# DigitalCapture.net
KiCad netlist of a schematic drawn in Altium Designer
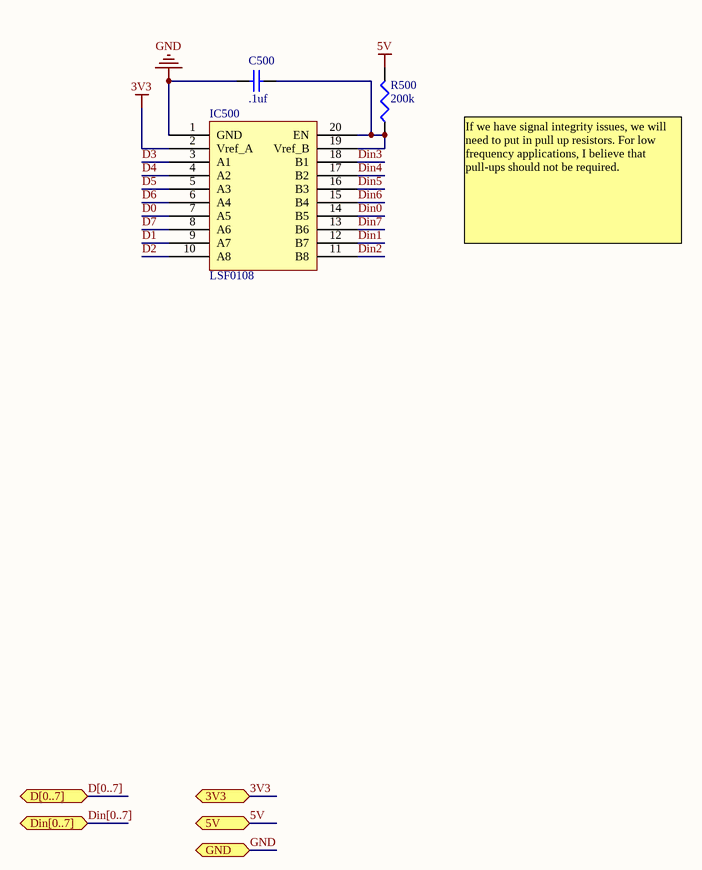
[diagram p0: DigitalCapture.SchDoc]

(export (version "E")
  (design (tool "Eeschema 10.0.6"))
  (components
    (comp (ref "C500")
      (value ".1uf")
      (footprint "SMD0603")
      (description "Ceramic Chip Capacitor")
      (fields (field (name "Comment") "Cap"))
      (libsource (lib "Components") (part "Capacitor Ceramic"))
    )
    (comp (ref "IC500")
      (value "LSF0108")
      (footprint "TSSOP-20")
      (description "8 bit 5V to 3.3V level shifter")
      (libsource (lib "Components") (part "LSF0108"))
    )
    (comp (ref "R500")
      (value "200k")
      (footprint "SMD0603")
      (description "Resistor")
      (fields (field (name "Comment") "Res"))
      (libsource (lib "Components") (part "Resistor"))
    )
  )
  (nets
    (net (code "1") (name "/D0") (class "Default")
      (node (ref "IC500") (pin "7") (pinfunction "A5_7") (pintype "passive"))
    )
    (net (code "2") (name "/D1") (class "Default")
      (node (ref "IC500") (pin "9") (pinfunction "A7_9") (pintype "passive"))
    )
    (net (code "3") (name "/D2") (class "Default")
      (node (ref "IC500") (pin "10") (pinfunction "A8_10") (pintype "passive"))
    )
    (net (code "4") (name "/D3") (class "Default")
      (node (ref "IC500") (pin "3") (pinfunction "A1_3") (pintype "passive"))
    )
    (net (code "5") (name "/D4") (class "Default")
      (node (ref "IC500") (pin "4") (pinfunction "A2_4") (pintype "passive"))
    )
    (net (code "6") (name "/D5") (class "Default")
      (node (ref "IC500") (pin "5") (pinfunction "A3_5") (pintype "passive"))
    )
    (net (code "7") (name "/D6") (class "Default")
      (node (ref "IC500") (pin "6") (pinfunction "A4_6") (pintype "passive"))
    )
    (net (code "8") (name "/D7") (class "Default")
      (node (ref "IC500") (pin "8") (pinfunction "A6_8") (pintype "passive"))
    )
    (net (code "10") (name "/Din0") (class "Default")
      (node (ref "IC500") (pin "14") (pinfunction "B5_14") (pintype "passive"))
    )
    (net (code "11") (name "/Din1") (class "Default")
      (node (ref "IC500") (pin "12") (pinfunction "B7_12") (pintype "passive"))
    )
    (net (code "12") (name "/Din2") (class "Default")
      (node (ref "IC500") (pin "11") (pinfunction "B8_11") (pintype "passive"))
    )
    (net (code "13") (name "/Din3") (class "Default")
      (node (ref "IC500") (pin "18") (pinfunction "B1_18") (pintype "passive"))
    )
    (net (code "14") (name "/Din4") (class "Default")
      (node (ref "IC500") (pin "17") (pinfunction "B2_17") (pintype "passive"))
    )
    (net (code "15") (name "/Din5") (class "Default")
      (node (ref "IC500") (pin "16") (pinfunction "B3_16") (pintype "passive"))
    )
    (net (code "16") (name "/Din6") (class "Default")
      (node (ref "IC500") (pin "15") (pinfunction "B4_15") (pintype "passive"))
    )
    (net (code "17") (name "/Din7") (class "Default")
      (node (ref "IC500") (pin "13") (pinfunction "B6_13") (pintype "passive"))
    )
    (net (code "19") (name "3V3") (class "Default")
      (node (ref "IC500") (pin "2") (pinfunction "Vref_A_2") (pintype "passive"))
    )
    (net (code "20") (name "5V") (class "Default")
      (node (ref "R500") (pin "2") (pinfunction "2_2") (pintype "passive"))
    )
    (net (code "21") (name "GND") (class "Default")
      (node (ref "C500") (pin "2") (pinfunction "2_2") (pintype "passive"))
      (node (ref "IC500") (pin "1") (pinfunction "GND_1") (pintype "passive"))
    )
    (net (code "22") (name "Net-(IC500-EN)") (class "Default")
      (node (ref "C500") (pin "1") (pinfunction "1_1") (pintype "passive"))
      (node (ref "IC500") (pin "19") (pinfunction "Vref_B_19") (pintype "passive"))
      (node (ref "IC500") (pin "20") (pinfunction "EN_20") (pintype "passive"))
      (node (ref "R500") (pin "1") (pinfunction "1_1") (pintype "passive"))
    )
  )
)
